# Digital_Input.net
KiCad netlist of a schematic drawn in Altium Designer
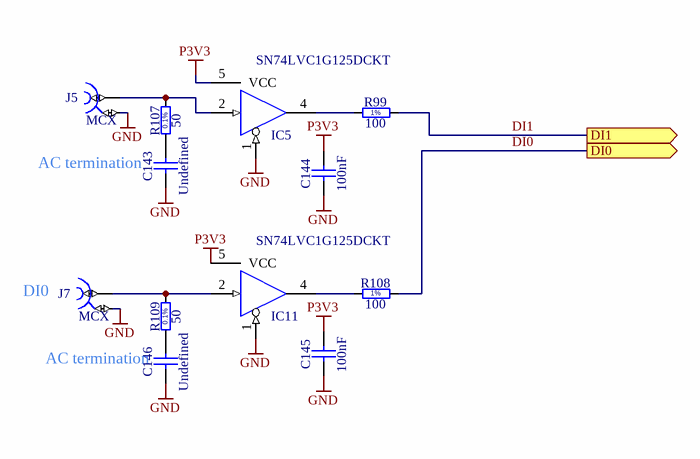
[diagram p0: Digital_Input.SchDoc]

(export (version "E")
  (design (tool "Eeschema 10.0.6"))
  (components
    (comp (ref "C143")
      (value "Undefined")
      (footprint "CAPC1608X90N")
      (description "Non-polarised capacitor")
      (fields (field (name "PART NUMBER") "CC0603_NO-VALUE") (field (name "AUTHOR") "CERN DEM MR"))
      (libsource (lib "Capacitors") (part "Capacitor - non polarized"))
    )
    (comp (ref "C144")
      (value "100nF")
      (footprint "CAPC1005X55N")
      (description "Non-polarised capacitor")
      (fields
        (field (name "PART NUMBER") "CC0402_100NF_16V_10%_X7R")
        (field (name "VOLTAGE") "16V")
        (field (name "AUTHOR") "CERN DEM JLC")
      )
      (libsource (lib "Capacitors") (part "Capacitor - non polarized"))
    )
    (comp (ref "C145")
      (value "100nF")
      (footprint "CAPC1005X55N")
      (description "Non-polarised capacitor")
      (fields
        (field (name "PART NUMBER") "CC0402_100NF_16V_10%_X7R")
        (field (name "VOLTAGE") "16V")
        (field (name "AUTHOR") "CERN DEM JLC")
      )
      (libsource (lib "Capacitors") (part "Capacitor - non polarized"))
    )
    (comp (ref "C146")
      (value "Undefined")
      (footprint "CAPC1608X90N")
      (description "Non-polarised capacitor")
      (fields (field (name "PART NUMBER") "CC0603_NO-VALUE") (field (name "AUTHOR") "CERN DEM MR"))
      (libsource (lib "Capacitors") (part "Capacitor - non polarized"))
    )
    (comp (ref "IC5")
      (value "SN74LVC1G125DCKT")
      (footprint "SOT65P210X110-5N")
      (description "Single Bus Buffer Gate With 3-State Output")
      (fields (field (name "MANUFACTURER") "TEXAS INSTRUMENTS") (field (name "AUTHOR") "CERN DEM JLC"))
      (libsource (lib "ICs And Semiconductors") (part "741G125"))
    )
    (comp (ref "IC11")
      (value "SN74LVC1G125DCKT")
      (footprint "SOT65P210X110-5N")
      (description "Single Bus Buffer Gate With 3-State Output")
      (fields (field (name "MANUFACTURER") "TEXAS INSTRUMENTS") (field (name "AUTHOR") "CERN DEM JLC"))
      (libsource (lib "ICs And Semiconductors") (part "741G125"))
    )
    (comp (ref "J5")
      (value "MCX")
      (footprint "AMPHENOL_919-383J-51A")
      (fields
        (field (name "PART NUMBER") "AMPHENOL_919-383J-51A")
        (field (name "MANUFACTURER") "AMPHENOL")
        (field (name "MANUFACTURER PART NUMBER") "919-383J-51A")
        (field (name "AUTHOR") "CERN DEM BC")
      )
      (libsource (lib "Connectors") (part "Coax_1Female_1Shield"))
    )
    (comp (ref "J7")
      (value "MCX")
      (footprint "AMPHENOL_919-383J-51A")
      (fields
        (field (name "PART NUMBER") "AMPHENOL_919-383J-51A")
        (field (name "MANUFACTURER") "AMPHENOL")
        (field (name "MANUFACTURER PART NUMBER") "919-383J-51A")
        (field (name "AUTHOR") "CERN DEM BC")
      )
      (libsource (lib "Connectors") (part "Coax_1Female_1Shield"))
    )
    (comp (ref "R99")
      (value "100")
      (footprint "RESC1005X40N")
      (description "Resistor - 1%")
      (fields
        (field (name "PART NUMBER") "R0402_100R_1%_0.1W_100PPM")
        (field (name "POWER") "0.1W")
        (field (name "AUTHOR") "CERN DEM JLC")
      )
      (libsource (lib "Resistors") (part "Resistor - 1%"))
    )
    (comp (ref "R107")
      (value "50")
      (footprint "RESC1005X35N")
      (description "Resistor - 0.1%")
      (fields
        (field (name "PART NUMBER") "R0402_50R_0.1%_0.05W_25PPM")
        (field (name "POWER") "0.05W")
        (field (name "AUTHOR") "CERN DEM JMW")
      )
      (libsource (lib "Resistors") (part "Resistor - 0.1%"))
    )
    (comp (ref "R108")
      (value "100")
      (footprint "RESC1005X40N")
      (description "Resistor - 1%")
      (fields
        (field (name "PART NUMBER") "R0402_100R_1%_0.1W_100PPM")
        (field (name "POWER") "0.1W")
        (field (name "AUTHOR") "CERN DEM JLC")
      )
      (libsource (lib "Resistors") (part "Resistor - 1%"))
    )
    (comp (ref "R109")
      (value "50")
      (footprint "RESC1005X35N")
      (description "Resistor - 0.1%")
      (fields
        (field (name "PART NUMBER") "R0402_50R_0.1%_0.05W_25PPM")
        (field (name "POWER") "0.05W")
        (field (name "AUTHOR") "CERN DEM JMW")
      )
      (libsource (lib "Resistors") (part "Resistor - 0.1%"))
    )
  )
  (nets
    (net (code "1") (name "/DI0") (class "Default")
      (node (ref "R108") (pin "2") (pinfunction "2_2") (pintype "passive"))
    )
    (net (code "2") (name "/DI1") (class "Default")
      (node (ref "R99") (pin "2") (pinfunction "2_2") (pintype "passive"))
    )
    (net (code "3") (name "GND") (class "Default")
      (node (ref "C143") (pin "1") (pinfunction "1_1") (pintype "passive"))
      (node (ref "C144") (pin "1") (pinfunction "1_1") (pintype "passive"))
      (node (ref "C145") (pin "1") (pinfunction "1_1") (pintype "passive"))
      (node (ref "C146") (pin "1") (pinfunction "1_1") (pintype "passive"))
      (node (ref "IC11") (pin "1") (pinfunction "~{G}_1") (pintype "input"))
      (node (ref "IC11") (pin "3") (pinfunction "GND_3") (pintype "power_in"))
      (node (ref "IC5") (pin "1") (pinfunction "~{G}_1") (pintype "input"))
      (node (ref "IC5") (pin "3") (pinfunction "GND_3") (pintype "power_in"))
      (node (ref "J5") (pin "2") (pinfunction "2_2") (pintype "bidirectional"))
      (node (ref "J7") (pin "2") (pinfunction "2_2") (pintype "bidirectional"))
    )
    (net (code "4") (name "Net-(C143-Pad2)") (class "Default")
      (node (ref "C143") (pin "2") (pinfunction "2_2") (pintype "passive"))
      (node (ref "R107") (pin "1") (pinfunction "1_1") (pintype "passive"))
    )
    (net (code "5") (name "Net-(C146-Pad2)") (class "Default")
      (node (ref "C146") (pin "2") (pinfunction "2_2") (pintype "passive"))
      (node (ref "R109") (pin "1") (pinfunction "1_1") (pintype "passive"))
    )
    (net (code "6") (name "Net-(IC5-IN)") (class "Default")
      (node (ref "IC5") (pin "2") (pinfunction "IN_2") (pintype "input"))
      (node (ref "J5") (pin "1") (pinfunction "1_1") (pintype "bidirectional"))
      (node (ref "R107") (pin "2") (pinfunction "2_2") (pintype "passive"))
    )
    (net (code "7") (name "Net-(IC5-OUT)") (class "Default")
      (node (ref "IC5") (pin "4") (pinfunction "OUT_4") (pintype "tri_state"))
      (node (ref "R99") (pin "1") (pinfunction "1_1") (pintype "passive"))
    )
    (net (code "8") (name "Net-(IC11-IN)") (class "Default")
      (node (ref "IC11") (pin "2") (pinfunction "IN_2") (pintype "input"))
      (node (ref "J7") (pin "1") (pinfunction "1_1") (pintype "bidirectional"))
      (node (ref "R109") (pin "2") (pinfunction "2_2") (pintype "passive"))
    )
    (net (code "9") (name "Net-(IC11-OUT)") (class "Default")
      (node (ref "IC11") (pin "4") (pinfunction "OUT_4") (pintype "tri_state"))
      (node (ref "R108") (pin "1") (pinfunction "1_1") (pintype "passive"))
    )
    (net (code "10") (name "P3V3") (class "Default")
      (node (ref "C144") (pin "2") (pinfunction "2_2") (pintype "passive"))
      (node (ref "C145") (pin "2") (pinfunction "2_2") (pintype "passive"))
      (node (ref "IC11") (pin "5") (pinfunction "VCC_5") (pintype "power_in"))
      (node (ref "IC5") (pin "5") (pinfunction "VCC_5") (pintype "power_in"))
    )
  )
)
